# PCB1.net
KiCad netlist of a schematic drawn in Altium Designer
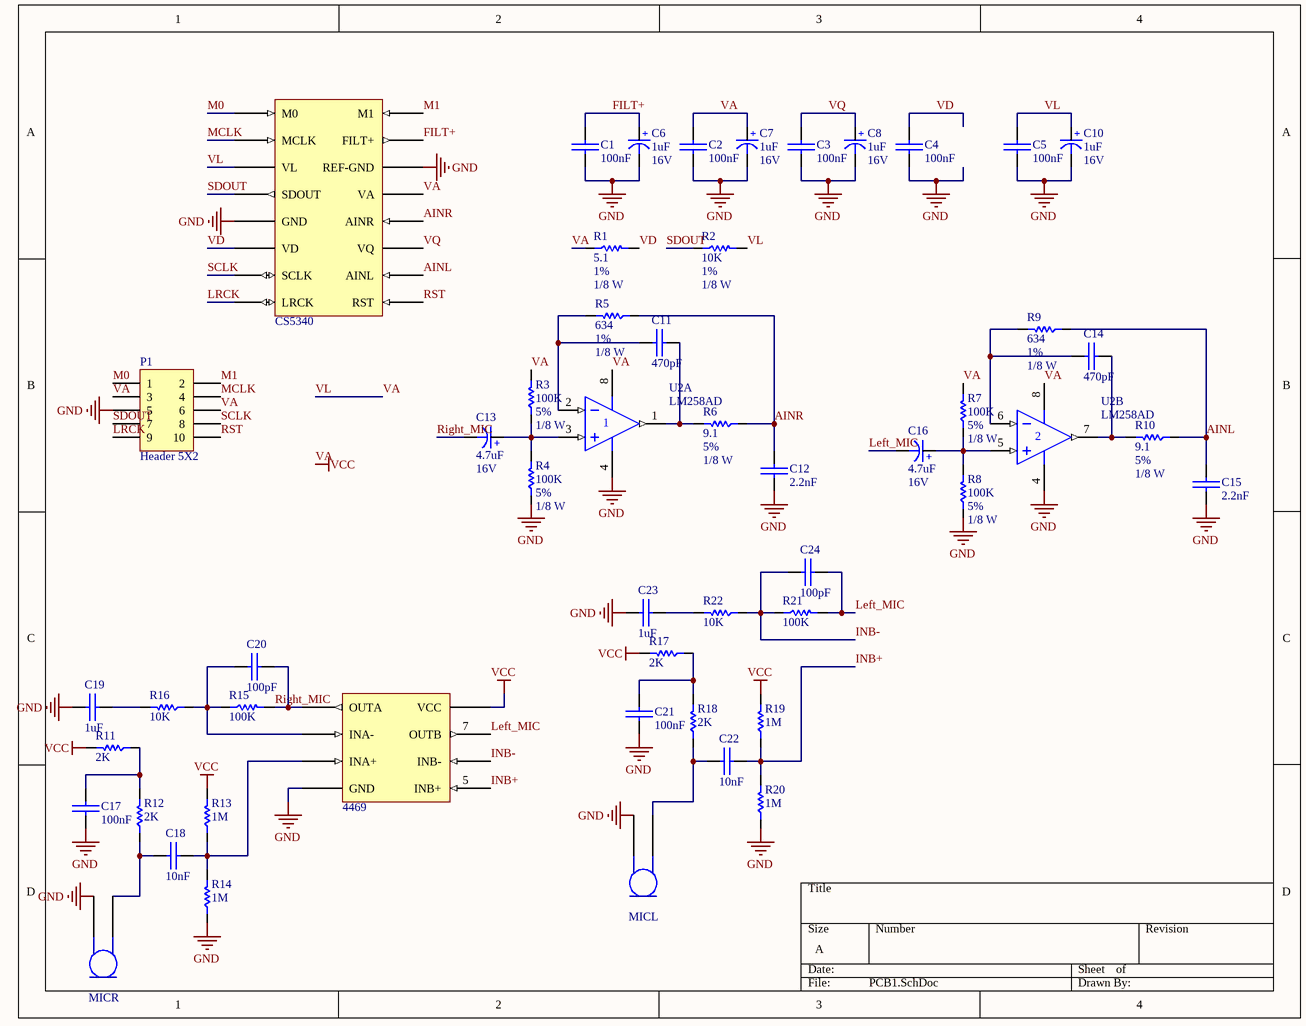
[diagram p0: PCB1.SchDoc]

(export (version "E")
  (design (tool "Eeschema 10.0.6"))
  (components
    (comp (ref "4469")
      (value "MAX4469EKA+T")
      (footprint "SOT23-8_L")
      (description "Low-Cost, Micropower, SC70/SOT23-8, Microphone Preamplifier")
      (libsource (lib "FB_Altium_Library") (part "MAX4469EKA+T"))
    )
    (comp (ref "C1")
      (value "100nF")
      (footprint "SMD_CAP_1206")
      (description "Bipolar Capacitor")
      (fields (field (name "VOLTAGE") "100V") (field (name "DESIGNER") "Saeid Jorablo"))
      (libsource (lib "My Library") (part "Cap-Bipolar"))
    )
    (comp (ref "C2")
      (value "100nF")
      (footprint "SMD_CAP_1206")
      (description "Bipolar Capacitor")
      (fields (field (name "VOLTAGE") "100V") (field (name "DESIGNER") "Saeid Jorablo"))
      (libsource (lib "My Library") (part "Cap-Bipolar"))
    )
    (comp (ref "C3")
      (value "100nF")
      (footprint "SMD_CAP_1206")
      (description "Bipolar Capacitor")
      (fields (field (name "VOLTAGE") "100V") (field (name "DESIGNER") "Saeid Jorablo"))
      (libsource (lib "My Library") (part "Cap-Bipolar"))
    )
    (comp (ref "C4")
      (value "100nF")
      (footprint "SMD_CAP_1206")
      (description "Bipolar Capacitor")
      (fields (field (name "VOLTAGE") "100V") (field (name "DESIGNER") "Saeid Jorablo"))
      (libsource (lib "My Library") (part "Cap-Bipolar"))
    )
    (comp (ref "C5")
      (value "100nF")
      (footprint "SMD_CAP_1206")
      (description "Bipolar Capacitor")
      (fields (field (name "VOLTAGE") "100V") (field (name "DESIGNER") "Saeid Jorablo"))
      (libsource (lib "My Library") (part "Cap-Bipolar"))
    )
    (comp (ref "C6")
      (value "1uF")
      (footprint "CAPP 1206 (3216X18L) Size A")
      (description "Polar Capacitor")
      (fields (field (name "VOLTAGE") "16V") (field (name "DESIGNER") "Saeid Jorablo"))
      (libsource (lib "My Library") (part "Cap-Polar"))
    )
    (comp (ref "C7")
      (value "1uF")
      (footprint "CAPP 1206 (3216X18L) Size A")
      (description "Polar Capacitor")
      (fields (field (name "VOLTAGE") "16V") (field (name "DESIGNER") "Saeid Jorablo"))
      (libsource (lib "My Library") (part "Cap-Polar"))
    )
    (comp (ref "C8")
      (value "1uF")
      (footprint "CAPP 1206 (3216X18L) Size A")
      (description "Polar Capacitor")
      (fields (field (name "VOLTAGE") "16V") (field (name "DESIGNER") "Saeid Jorablo"))
      (libsource (lib "My Library") (part "Cap-Polar"))
    )
    (comp (ref "C10")
      (value "1uF")
      (footprint "CAPP 1206 (3216X18L) Size A")
      (description "Polar Capacitor")
      (fields (field (name "VOLTAGE") "16V") (field (name "DESIGNER") "Saeid Jorablo"))
      (libsource (lib "My Library") (part "Cap-Polar"))
    )
    (comp (ref "C11")
      (value "470pF")
      (footprint "SMD_CAP_1206")
      (description "Bipolar Capacitor")
      (fields (field (name "VOLTAGE") "100V") (field (name "DESIGNER") "Saeid Jorablo"))
      (libsource (lib "My Library") (part "Cap-Bipolar"))
    )
    (comp (ref "C12")
      (value "2.2nF")
      (footprint "SMD_CAP_1206")
      (description "Bipolar Capacitor")
      (fields (field (name "VOLTAGE") "100V") (field (name "DESIGNER") "Saeid Jorablo"))
      (libsource (lib "My Library") (part "Cap-Bipolar"))
    )
    (comp (ref "C13")
      (value "4.7uF")
      (footprint "CAPP 1206 (3216X18L) Size A")
      (description "Polar Capacitor")
      (fields (field (name "VOLTAGE") "16V") (field (name "DESIGNER") "Saeid Jorablo"))
      (libsource (lib "My Library") (part "Cap-Polar"))
    )
    (comp (ref "C14")
      (value "470pF")
      (footprint "SMD_CAP_1206")
      (description "Bipolar Capacitor")
      (fields (field (name "VOLTAGE") "100V") (field (name "DESIGNER") "Saeid Jorablo"))
      (libsource (lib "My Library") (part "Cap-Bipolar"))
    )
    (comp (ref "C15")
      (value "2.2nF")
      (footprint "SMD_CAP_1206")
      (description "Bipolar Capacitor")
      (fields (field (name "VOLTAGE") "100V") (field (name "DESIGNER") "Saeid Jorablo"))
      (libsource (lib "My Library") (part "Cap-Bipolar"))
    )
    (comp (ref "C16")
      (value "4.7uF")
      (footprint "CAPP 1206 (3216X18L) Size A")
      (description "Polar Capacitor")
      (fields (field (name "VOLTAGE") "16V") (field (name "DESIGNER") "Saeid Jorablo"))
      (libsource (lib "My Library") (part "Cap-Polar"))
    )
    (comp (ref "C17")
      (value "100nF")
      (footprint "SMD_CAP_1206")
      (description "Bipolar Capacitor")
      (fields (field (name "VOLTAGE") "100V") (field (name "DESIGNER") "Saeid Jorablo"))
      (libsource (lib "My Library") (part "Cap-Bipolar"))
    )
    (comp (ref "C18")
      (value "10nF")
      (footprint "SMD_CAP_1206")
      (description "Bipolar Capacitor")
      (fields (field (name "VOLTAGE") "100V") (field (name "DESIGNER") "Saeid Jorablo"))
      (libsource (lib "My Library") (part "Cap-Bipolar"))
    )
    (comp (ref "C19")
      (value "1uF")
      (footprint "SMD_CAP_1206")
      (description "Bipolar Capacitor")
      (fields (field (name "VOLTAGE") "100V") (field (name "DESIGNER") "Saeid Jorablo"))
      (libsource (lib "My Library") (part "Cap-Bipolar"))
    )
    (comp (ref "C20")
      (value "100pF")
      (footprint "SMD_CAP_1206")
      (description "Bipolar Capacitor")
      (fields (field (name "VOLTAGE") "100V") (field (name "DESIGNER") "Saeid Jorablo"))
      (libsource (lib "My Library") (part "Cap-Bipolar"))
    )
    (comp (ref "C21")
      (value "100nF")
      (footprint "SMD_CAP_1206")
      (description "Bipolar Capacitor")
      (fields (field (name "VOLTAGE") "100V") (field (name "DESIGNER") "Saeid Jorablo"))
      (libsource (lib "My Library") (part "Cap-Bipolar"))
    )
    (comp (ref "C22")
      (value "10nF")
      (footprint "SMD_CAP_1206")
      (description "Bipolar Capacitor")
      (fields (field (name "VOLTAGE") "100V") (field (name "DESIGNER") "Saeid Jorablo"))
      (libsource (lib "My Library") (part "Cap-Bipolar"))
    )
    (comp (ref "C23")
      (value "1uF")
      (footprint "SMD_CAP_1206")
      (description "Bipolar Capacitor")
      (fields (field (name "VOLTAGE") "100V") (field (name "DESIGNER") "Saeid Jorablo"))
      (libsource (lib "My Library") (part "Cap-Bipolar"))
    )
    (comp (ref "C24")
      (value "100pF")
      (footprint "SMD_CAP_1206")
      (description "Bipolar Capacitor")
      (fields (field (name "VOLTAGE") "100V") (field (name "DESIGNER") "Saeid Jorablo"))
      (libsource (lib "My Library") (part "Cap-Bipolar"))
    )
    (comp (ref "CS5340")
      (value "CS5340-CZZ")
      (footprint "TSSOP16_L")
      (description "ADC, Audio 24 bit 192k Serial 16-TSSOP")
      (libsource (lib "FB_Altium_Library") (part "CS5340-CZZ"))
    )
    (comp (ref "MICL")
      (value "Electret Microphone 10mm")
      (footprint "MIC1")
      (libsource (lib "FB_Altium_Library") (part "Microphone"))
    )
    (comp (ref "MICR")
      (value "Electret Microphone 10mm")
      (footprint "MIC1")
      (libsource (lib "FB_Altium_Library") (part "Microphone"))
    )
    (comp (ref "P1")
      (value "Header 5X2")
      (footprint "FKV10LN")
      (description "Header, 5-Pin, Dual row")
      (fields (field (name "PUBLISHER") "Altium Limited"))
      (libsource (lib "Miscellaneous Connectors") (part "Header 5X2"))
    )
    (comp (ref "R1")
      (value "5.1")
      (footprint "RES 1206 (3216X08L)")
      (description "Resistor")
      (fields (field (name "TOLERANCE") "1%") (field (name "POWER") "1/8 W"))
      (libsource (lib "My Library") (part "Resistor"))
    )
    (comp (ref "R2")
      (value "10K")
      (footprint "RES 1206 (3216X08L)")
      (description "Resistor")
      (fields (field (name "TOLERANCE") "1%") (field (name "POWER") "1/8 W"))
      (libsource (lib "My Library") (part "Resistor"))
    )
    (comp (ref "R3")
      (value "100K")
      (footprint "RES 1206 (3216X08L)")
      (description "Resistor")
      (fields (field (name "TOLERANCE") "5%") (field (name "POWER") "1/8 W"))
      (libsource (lib "My Library") (part "Resistor"))
    )
    (comp (ref "R4")
      (value "100K")
      (footprint "RES 1206 (3216X08L)")
      (description "Resistor")
      (fields (field (name "TOLERANCE") "5%") (field (name "POWER") "1/8 W"))
      (libsource (lib "My Library") (part "Resistor"))
    )
    (comp (ref "R5")
      (value "634")
      (footprint "RES 1206 (3216X08L)")
      (description "Resistor")
      (fields (field (name "TOLERANCE") "1%") (field (name "POWER") "1/8 W"))
      (libsource (lib "My Library") (part "Resistor"))
    )
    (comp (ref "R6")
      (value "9.1")
      (footprint "RES 1206 (3216X08L)")
      (description "Resistor")
      (fields (field (name "TOLERANCE") "5%") (field (name "POWER") "1/8 W"))
      (libsource (lib "My Library") (part "Resistor"))
    )
    (comp (ref "R7")
      (value "100K")
      (footprint "RES 1206 (3216X08L)")
      (description "Resistor")
      (fields (field (name "TOLERANCE") "5%") (field (name "POWER") "1/8 W"))
      (libsource (lib "My Library") (part "Resistor"))
    )
    (comp (ref "R8")
      (value "100K")
      (footprint "RES 1206 (3216X08L)")
      (description "Resistor")
      (fields (field (name "TOLERANCE") "5%") (field (name "POWER") "1/8 W"))
      (libsource (lib "My Library") (part "Resistor"))
    )
    (comp (ref "R9")
      (value "634")
      (footprint "RES 1206 (3216X08L)")
      (description "Resistor")
      (fields (field (name "TOLERANCE") "1%") (field (name "POWER") "1/8 W"))
      (libsource (lib "My Library") (part "Resistor"))
    )
    (comp (ref "R10")
      (value "9.1")
      (footprint "RES 1206 (3216X08L)")
      (description "Resistor")
      (fields (field (name "TOLERANCE") "5%") (field (name "POWER") "1/8 W"))
      (libsource (lib "My Library") (part "Resistor"))
    )
    (comp (ref "R11")
      (value "2K")
      (footprint "RES 1206 (3216X08L)")
      (description "Resistor")
      (fields (field (name "TOLERANCE") "5%") (field (name "POWER") "1/8 W"))
      (libsource (lib "My Library") (part "Resistor"))
    )
    (comp (ref "R12")
      (value "2K")
      (footprint "RES 1206 (3216X08L)")
      (description "Resistor")
      (fields (field (name "TOLERANCE") "5%") (field (name "POWER") "1/8 W"))
      (libsource (lib "My Library") (part "Resistor"))
    )
    (comp (ref "R13")
      (value "1M")
      (footprint "RES 1206 (3216X08L)")
      (description "Resistor")
      (fields (field (name "TOLERANCE") "5%") (field (name "POWER") "1/8 W"))
      (libsource (lib "My Library") (part "Resistor"))
    )
    (comp (ref "R14")
      (value "1M")
      (footprint "RES 1206 (3216X08L)")
      (description "Resistor")
      (fields (field (name "TOLERANCE") "5%") (field (name "POWER") "1/8 W"))
      (libsource (lib "My Library") (part "Resistor"))
    )
    (comp (ref "R15")
      (value "100K")
      (footprint "RES 1206 (3216X08L)")
      (description "Resistor")
      (fields (field (name "TOLERANCE") "5%") (field (name "POWER") "1/8 W"))
      (libsource (lib "My Library") (part "Resistor"))
    )
    (comp (ref "R16")
      (value "10K")
      (footprint "RES 1206 (3216X08L)")
      (description "Resistor")
      (fields (field (name "TOLERANCE") "5%") (field (name "POWER") "1/8 W"))
      (libsource (lib "My Library") (part "Resistor"))
    )
    (comp (ref "R17")
      (value "2K")
      (footprint "RES 1206 (3216X08L)")
      (description "Resistor")
      (fields (field (name "TOLERANCE") "5%") (field (name "POWER") "1/8 W"))
      (libsource (lib "My Library") (part "Resistor"))
    )
    (comp (ref "R18")
      (value "2K")
      (footprint "RES 1206 (3216X08L)")
      (description "Resistor")
      (fields (field (name "TOLERANCE") "5%") (field (name "POWER") "1/8 W"))
      (libsource (lib "My Library") (part "Resistor"))
    )
    (comp (ref "R19")
      (value "1M")
      (footprint "RES 1206 (3216X08L)")
      (description "Resistor")
      (fields (field (name "TOLERANCE") "5%") (field (name "POWER") "1/8 W"))
      (libsource (lib "My Library") (part "Resistor"))
    )
    (comp (ref "R20")
      (value "1M")
      (footprint "RES 1206 (3216X08L)")
      (description "Resistor")
      (fields (field (name "TOLERANCE") "5%") (field (name "POWER") "1/8 W"))
      (libsource (lib "My Library") (part "Resistor"))
    )
    (comp (ref "R21")
      (value "100K")
      (footprint "RES 1206 (3216X08L)")
      (description "Resistor")
      (fields (field (name "TOLERANCE") "5%") (field (name "POWER") "1/8 W"))
      (libsource (lib "My Library") (part "Resistor"))
    )
    (comp (ref "R22")
      (value "10K")
      (footprint "RES 1206 (3216X08L)")
      (description "Resistor")
      (fields (field (name "TOLERANCE") "5%") (field (name "POWER") "1/8 W"))
      (libsource (lib "My Library") (part "Resistor"))
    )
    (comp (ref "U2")
      (value "LM258AD")
      (footprint "D008_L")
      (description "Dual Operational Amplifier")
      (fields (field (name "PUBLISHER") "Altium Limited"))
      (libsource (lib "TI Operational Amplifier") (part "LM258AD"))
    )
  )
  (nets
    (net (code "1") (name "/AINL") (class "Default")
      (node (ref "C15") (pin "1") (pinfunction "+_1") (pintype "passive"))
      (node (ref "CS5340") (pin "10") (pinfunction "AINL_10") (pintype "input"))
      (node (ref "R10") (pin "1") (pinfunction "1_1") (pintype "passive"))
      (node (ref "R9") (pin "1") (pinfunction "1_1") (pintype "passive"))
    )
    (net (code "2") (name "/AINR") (class "Default")
      (node (ref "C12") (pin "1") (pinfunction "+_1") (pintype "passive"))
      (node (ref "CS5340") (pin "12") (pinfunction "AINR_12") (pintype "input"))
      (node (ref "R5") (pin "1") (pinfunction "1_1") (pintype "passive"))
      (node (ref "R6") (pin "1") (pinfunction "1_1") (pintype "passive"))
    )
    (net (code "3") (name "/FILT+") (class "Default")
      (node (ref "C1") (pin "1") (pinfunction "+_1") (pintype "passive"))
      (node (ref "C6") (pin "1") (pinfunction "+_1") (pintype "passive"))
      (node (ref "CS5340") (pin "15") (pinfunction "FILT+_15") (pintype "output"))
    )
    (net (code "4") (name "/INB+") (class "Default")
      (node (ref "4469") (pin "5") (pinfunction "INB+_5") (pintype "input"))
      (node (ref "C22") (pin "2") (pinfunction "-_2") (pintype "passive"))
      (node (ref "R19") (pin "1") (pinfunction "1_1") (pintype "passive"))
      (node (ref "R20") (pin "2") (pinfunction "2_2") (pintype "passive"))
    )
    (net (code "5") (name "/INB-") (class "Default")
      (node (ref "4469") (pin "6") (pinfunction "INB-_6") (pintype "input"))
      (node (ref "C24") (pin "1") (pinfunction "+_1") (pintype "passive"))
      (node (ref "R21") (pin "1") (pinfunction "1_1") (pintype "passive"))
      (node (ref "R22") (pin "1") (pinfunction "1_1") (pintype "passive"))
    )
    (net (code "6") (name "/LRCK") (class "Default")
      (node (ref "CS5340") (pin "8") (pinfunction "LRCK_8") (pintype "bidirectional"))
      (node (ref "P1") (pin "9") (pinfunction "9_9") (pintype "passive"))
    )
    (net (code "7") (name "/Left_MIC") (class "Default")
      (node (ref "4469") (pin "7") (pinfunction "OUTB_7") (pintype "output"))
      (node (ref "C16") (pin "2") (pinfunction "-_2") (pintype "passive"))
      (node (ref "C24") (pin "2") (pinfunction "-_2") (pintype "passive"))
      (node (ref "R21") (pin "2") (pinfunction "2_2") (pintype "passive"))
    )
    (net (code "8") (name "/M0") (class "Default")
      (node (ref "CS5340") (pin "1") (pinfunction "M0_1") (pintype "input"))
      (node (ref "P1") (pin "1") (pinfunction "1_1") (pintype "passive"))
    )
    (net (code "9") (name "/M1") (class "Default")
      (node (ref "CS5340") (pin "16") (pinfunction "M1_16") (pintype "input"))
      (node (ref "P1") (pin "2") (pinfunction "2_2") (pintype "passive"))
    )
    (net (code "10") (name "/MCLK") (class "Default")
      (node (ref "CS5340") (pin "2") (pinfunction "MCLK_2") (pintype "input"))
      (node (ref "P1") (pin "4") (pinfunction "4_4") (pintype "passive"))
    )
    (net (code "11") (name "/RST") (class "Default")
      (node (ref "CS5340") (pin "9") (pinfunction "RST_9") (pintype "input"))
      (node (ref "P1") (pin "10") (pinfunction "10_10") (pintype "passive"))
    )
    (net (code "12") (name "/Right_MIC") (class "Default")
      (node (ref "4469") (pin "1") (pinfunction "OUTA_1") (pintype "output"))
      (node (ref "C13") (pin "2") (pinfunction "-_2") (pintype "passive"))
      (node (ref "C20") (pin "2") (pinfunction "-_2") (pintype "passive"))
      (node (ref "R15") (pin "2") (pinfunction "2_2") (pintype "passive"))
    )
    (net (code "13") (name "/SCLK") (class "Default")
      (node (ref "CS5340") (pin "7") (pinfunction "SCLK_7") (pintype "bidirectional"))
      (node (ref "P1") (pin "8") (pinfunction "8_8") (pintype "passive"))
    )
    (net (code "14") (name "/SDOUT") (class "Default")
      (node (ref "CS5340") (pin "4") (pinfunction "SDOUT_4") (pintype "output"))
      (node (ref "P1") (pin "7") (pinfunction "7_7") (pintype "passive"))
      (node (ref "R2") (pin "1") (pinfunction "1_1") (pintype "passive"))
    )
    (net (code "15") (name "/VD") (class "Default")
      (node (ref "C4") (pin "1") (pinfunction "+_1") (pintype "passive"))
      (node (ref "CS5340") (pin "6") (pinfunction "VD_6") (pintype "passive"))
      (node (ref "R1") (pin "2") (pinfunction "2_2") (pintype "passive"))
    )
    (net (code "16") (name "/VQ") (class "Default")
      (node (ref "C3") (pin "1") (pinfunction "+_1") (pintype "passive"))
      (node (ref "C8") (pin "1") (pinfunction "+_1") (pintype "passive"))
      (node (ref "CS5340") (pin "11") (pinfunction "VQ_11") (pintype "power_in"))
    )
    (net (code "17") (name "GND") (class "Default")
      (node (ref "4469") (pin "4") (pinfunction "GND_4") (pintype "power_in"))
      (node (ref "C1") (pin "2") (pinfunction "-_2") (pintype "passive"))
      (node (ref "C10") (pin "2") (pinfunction "-_2") (pintype "passive"))
      (node (ref "C12") (pin "2") (pinfunction "-_2") (pintype "passive"))
      (node (ref "C15") (pin "2") (pinfunction "-_2") (pintype "passive"))
      (node (ref "C17") (pin "1") (pinfunction "+_1") (pintype "passive"))
      (node (ref "C19") (pin "1") (pinfunction "+_1") (pintype "passive"))
      (node (ref "C2") (pin "2") (pinfunction "-_2") (pintype "passive"))
      (node (ref "C21") (pin "1") (pinfunction "+_1") (pintype "passive"))
      (node (ref "C23") (pin "1") (pinfunction "+_1") (pintype "passive"))
      (node (ref "C3") (pin "2") (pinfunction "-_2") (pintype "passive"))
      (node (ref "C4") (pin "2") (pinfunction "-_2") (pintype "passive"))
      (node (ref "C5") (pin "2") (pinfunction "-_2") (pintype "passive"))
      (node (ref "C6") (pin "2") (pinfunction "-_2") (pintype "passive"))
      (node (ref "C7") (pin "2") (pinfunction "-_2") (pintype "passive"))
      (node (ref "C8") (pin "2") (pinfunction "-_2") (pintype "passive"))
      (node (ref "CS5340") (pin "14") (pinfunction "REF-GND_14") (pintype "power_in"))
      (node (ref "CS5340") (pin "5") (pinfunction "GND_5") (pintype "power_in"))
      (node (ref "MICL") (pin "2") (pinfunction "2_2") (pintype "passive"))
      (node (ref "MICR") (pin "2") (pinfunction "2_2") (pintype "passive"))
      (node (ref "P1") (pin "5") (pinfunction "5_5") (pintype "passive"))
      (node (ref "R14") (pin "1") (pinfunction "1_1") (pintype "passive"))
      (node (ref "R20") (pin "1") (pinfunction "1_1") (pintype "passive"))
      (node (ref "R4") (pin "1") (pinfunction "1_1") (pintype "passive"))
      (node (ref "R8") (pin "1") (pinfunction "1_1") (pintype "passive"))
      (node (ref "U2") (pin "4") (pinfunction "V-_4") (pintype "power_in"))
    )
    (net (code "18") (name "Net-(4469-INA+)") (class "Default")
      (node (ref "4469") (pin "3") (pinfunction "INA+_3") (pintype "input"))
      (node (ref "C18") (pin "2") (pinfunction "-_2") (pintype "passive"))
      (node (ref "R13") (pin "1") (pinfunction "1_1") (pintype "passive"))
      (node (ref "R14") (pin "2") (pinfunction "2_2") (pintype "passive"))
    )
    (net (code "19") (name "Net-(4469-INA-)") (class "Default")
      (node (ref "4469") (pin "2") (pinfunction "INA-_2") (pintype "input"))
      (node (ref "C20") (pin "1") (pinfunction "+_1") (pintype "passive"))
      (node (ref "R15") (pin "1") (pinfunction "1_1") (pintype "passive"))
      (node (ref "R16") (pin "1") (pinfunction "1_1") (pintype "passive"))
    )
    (net (code "20") (name "Net-(C11-+)") (class "Default")
      (node (ref "C11") (pin "1") (pinfunction "+_1") (pintype "passive"))
      (node (ref "R5") (pin "2") (pinfunction "2_2") (pintype "passive"))
      (node (ref "U2") (pin "2") (pinfunction "IN-_2") (pintype "input"))
    )
    (net (code "21") (name "Net-(C11--)") (class "Default")
      (node (ref "C11") (pin "2") (pinfunction "-_2") (pintype "passive"))
      (node (ref "R6") (pin "2") (pinfunction "2_2") (pintype "passive"))
      (node (ref "U2") (pin "1") (pinfunction "OUT_1") (pintype "output"))
    )
    (net (code "22") (name "Net-(C13-+)") (class "Default")
      (node (ref "C13") (pin "1") (pinfunction "+_1") (pintype "passive"))
      (node (ref "R3") (pin "1") (pinfunction "1_1") (pintype "passive"))
      (node (ref "R4") (pin "2") (pinfunction "2_2") (pintype "passive"))
      (node (ref "U2") (pin "3") (pinfunction "IN+_3") (pintype "input"))
    )
    (net (code "23") (name "Net-(C14-+)") (class "Default")
      (node (ref "C14") (pin "1") (pinfunction "+_1") (pintype "passive"))
      (node (ref "R9") (pin "2") (pinfunction "2_2") (pintype "passive"))
      (node (ref "U2") (pin "6") (pinfunction "IN-_6") (pintype "input"))
    )
    (net (code "24") (name "Net-(C14--)") (class "Default")
      (node (ref "C14") (pin "2") (pinfunction "-_2") (pintype "passive"))
      (node (ref "R10") (pin "2") (pinfunction "2_2") (pintype "passive"))
      (node (ref "U2") (pin "7") (pinfunction "OUT_7") (pintype "output"))
    )
    (net (code "25") (name "Net-(C16-+)") (class "Default")
      (node (ref "C16") (pin "1") (pinfunction "+_1") (pintype "passive"))
      (node (ref "R7") (pin "1") (pinfunction "1_1") (pintype "passive"))
      (node (ref "R8") (pin "2") (pinfunction "2_2") (pintype "passive"))
      (node (ref "U2") (pin "5") (pinfunction "IN+_5") (pintype "input"))
    )
    (net (code "26") (name "Net-(C17--)") (class "Default")
      (node (ref "C17") (pin "2") (pinfunction "-_2") (pintype "passive"))
      (node (ref "R11") (pin "1") (pinfunction "1_1") (pintype "passive"))
      (node (ref "R12") (pin "2") (pinfunction "2_2") (pintype "passive"))
    )
    (net (code "27") (name "Net-(C18-+)") (class "Default")
      (node (ref "C18") (pin "1") (pinfunction "+_1") (pintype "passive"))
      (node (ref "MICR") (pin "1") (pinfunction "1_1") (pintype "passive"))
      (node (ref "R12") (pin "1") (pinfunction "1_1") (pintype "passive"))
    )
    (net (code "28") (name "Net-(C19--)") (class "Default")
      (node (ref "C19") (pin "2") (pinfunction "-_2") (pintype "passive"))
      (node (ref "R16") (pin "2") (pinfunction "2_2") (pintype "passive"))
    )
    (net (code "29") (name "Net-(C21--)") (class "Default")
      (node (ref "C21") (pin "2") (pinfunction "-_2") (pintype "passive"))
      (node (ref "R17") (pin "1") (pinfunction "1_1") (pintype "passive"))
      (node (ref "R18") (pin "2") (pinfunction "2_2") (pintype "passive"))
    )
    (net (code "30") (name "Net-(C22-+)") (class "Default")
      (node (ref "C22") (pin "1") (pinfunction "+_1") (pintype "passive"))
      (node (ref "MICL") (pin "1") (pinfunction "1_1") (pintype "passive"))
      (node (ref "R18") (pin "1") (pinfunction "1_1") (pintype "passive"))
    )
    (net (code "31") (name "Net-(C23--)") (class "Default")
      (node (ref "C23") (pin "2") (pinfunction "-_2") (pintype "passive"))
      (node (ref "R22") (pin "2") (pinfunction "2_2") (pintype "passive"))
    )
    (net (code "32") (name "VCC") (class "Default")
      (node (ref "4469") (pin "8") (pinfunction "VCC_8") (pintype "power_in"))
      (node (ref "C10") (pin "1") (pinfunction "+_1") (pintype "passive"))
      (node (ref "C2") (pin "1") (pinfunction "+_1") (pintype "passive"))
      (node (ref "C5") (pin "1") (pinfunction "+_1") (pintype "passive"))
      (node (ref "C7") (pin "1") (pinfunction "+_1") (pintype "passive"))
      (node (ref "CS5340") (pin "13") (pinfunction "VA_13") (pintype "power_in"))
      (node (ref "CS5340") (pin "3") (pinfunction "VL_3") (pintype "power_in"))
      (node (ref "P1") (pin "3") (pinfunction "3_3") (pintype "passive"))
      (node (ref "P1") (pin "6") (pinfunction "6_6") (pintype "passive"))
      (node (ref "R1") (pin "1") (pinfunction "1_1") (pintype "passive"))
      (node (ref "R11") (pin "2") (pinfunction "2_2") (pintype "passive"))
      (node (ref "R13") (pin "2") (pinfunction "2_2") (pintype "passive"))
      (node (ref "R17") (pin "2") (pinfunction "2_2") (pintype "passive"))
      (node (ref "R19") (pin "2") (pinfunction "2_2") (pintype "passive"))
      (node (ref "R2") (pin "2") (pinfunction "2_2") (pintype "passive"))
      (node (ref "R3") (pin "2") (pinfunction "2_2") (pintype "passive"))
      (node (ref "R7") (pin "2") (pinfunction "2_2") (pintype "passive"))
      (node (ref "U2") (pin "8") (pinfunction "V+_8") (pintype "power_in"))
    )
  )
)
